# main2.net
KiCad netlist of a schematic drawn in EAGLE
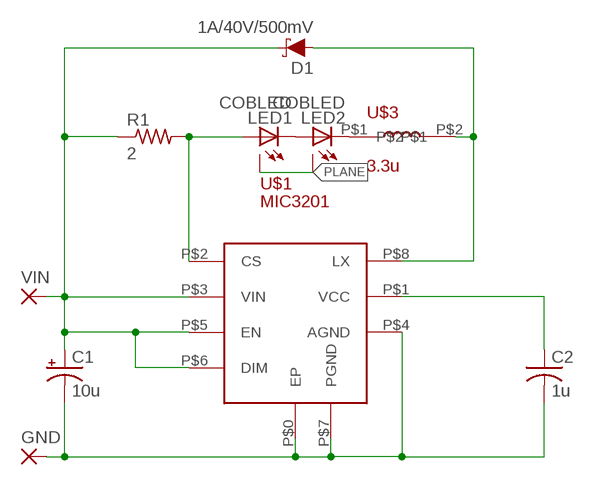
[diagram p0: schematic, sheet 1]

(export (version "E")
  (design (tool "Eeschema 10.0.6"))
  (components
    (comp (ref "C1")
      (value "10u")
      (footprint "eagle-import:E2-5")
      (libsource (lib "eagle-import") (part "CPOL-USE2-5"))
    )
    (comp (ref "C2")
      (value "1u")
      (footprint "eagle-import:C0805")
      (libsource (lib "eagle-import") (part "C-USC0805"))
    )
    (comp (ref "D1")
      (value "1A/40V/500mV")
      (footprint "eagle-import:SMA-DIODE")
      (libsource (lib "eagle-import") (part "DIODE-SCHOTTKY-SS14"))
    )
    (comp (ref "GND")
      (value "2,54/1,0")
      (footprint "eagle-import:2,54_1,0")
      (libsource (lib "eagle-import") (part "2,54/1,0"))
    )
    (comp (ref "LED1")
      (value "COBLED")
      (footprint "eagle-import:COBLED")
      (libsource (lib "eagle-import") (part "COBLED"))
    )
    (comp (ref "LED2")
      (value "COBLED")
      (footprint "eagle-import:COBLED")
      (libsource (lib "eagle-import") (part "COBLED"))
    )
    (comp (ref "R1")
      (value "2")
      (footprint "eagle-import:R0805")
      (libsource (lib "eagle-import") (part "R-US_R0805"))
    )
    (comp (ref "U$1")
      (value "MIC3201")
      (footprint "eagle-import:SOICNEP-8LD-LP-1")
      (libsource (lib "eagle-import") (part "MIC3201"))
    )
    (comp (ref "U$3")
      (value "3.3u")
      (footprint "eagle-import:DO1813H")
      (libsource (lib "eagle-import") (part "DO1813H"))
    )
    (comp (ref "VIN")
      (value "2,54/1,0")
      (footprint "eagle-import:2,54_1,0")
      (fields (field (name "SPICEPREFIX") "X"))
      (libsource (lib "eagle-import") (part "2,54/1,0"))
    )
  )
  (nets
    (net (code "1") (name "Net-(GND-P)") (class "Default")
      (node (ref "C1") (pin "-") (pinfunction "-_-") (pintype "passive"))
      (node (ref "C2") (pin "2") (pinfunction "2_2") (pintype "passive"))
      (node (ref "GND") (pin "1") (pinfunction "P_1") (pintype "passive"))
      (node (ref "U$1") (pin "P$0") (pinfunction "EP_P$0") (pintype "bidirectional"))
      (node (ref "U$1") (pin "P$4") (pinfunction "AGND_P$4") (pintype "bidirectional"))
      (node (ref "U$1") (pin "P$7") (pinfunction "PGND_P$7") (pintype "bidirectional"))
    )
    (net (code "2") (name "Net-(LED1-A)") (class "Default")
      (node (ref "LED1") (pin "P$1") (pinfunction "A_P$1") (pintype "passive"))
      (node (ref "R1") (pin "2") (pinfunction "2_2") (pintype "passive"))
      (node (ref "U$1") (pin "P$2") (pinfunction "CS_P$2") (pintype "bidirectional"))
    )
    (net (code "3") (name "Net-(LED1-C)") (class "Default")
      (node (ref "LED1") (pin "P$2") (pinfunction "C_P$2") (pintype "passive"))
      (node (ref "LED2") (pin "P$1") (pinfunction "A_P$1") (pintype "passive"))
    )
    (net (code "4") (name "Net-(LED2-C)") (class "Default")
      (node (ref "LED2") (pin "P$2") (pinfunction "C_P$2") (pintype "passive"))
      (node (ref "U$3") (pin "P$1") (pinfunction "P$1_P$1") (pintype "bidirectional"))
    )
    (net (code "5") (name "Net-(U$1-DIM)") (class "Default")
      (node (ref "C1") (pin "+") (pinfunction "+_+") (pintype "passive"))
      (node (ref "D1") (pin "C") (pinfunction "C_C") (pintype "passive"))
      (node (ref "R1") (pin "1") (pinfunction "1_1") (pintype "passive"))
      (node (ref "U$1") (pin "P$3") (pinfunction "VIN_P$3") (pintype "bidirectional"))
      (node (ref "U$1") (pin "P$5") (pinfunction "EN_P$5") (pintype "bidirectional"))
      (node (ref "U$1") (pin "P$6") (pinfunction "DIM_P$6") (pintype "bidirectional"))
      (node (ref "VIN") (pin "1") (pinfunction "P_1") (pintype "passive"))
    )
    (net (code "6") (name "Net-(U$1-LX)") (class "Default")
      (node (ref "D1") (pin "A") (pinfunction "A_A") (pintype "passive"))
      (node (ref "U$1") (pin "P$8") (pinfunction "LX_P$8") (pintype "bidirectional"))
      (node (ref "U$3") (pin "P$2") (pinfunction "P$2_P$2") (pintype "bidirectional"))
    )
    (net (code "7") (name "Net-(U$1-VCC)") (class "Default")
      (node (ref "C2") (pin "1") (pinfunction "1_1") (pintype "passive"))
      (node (ref "U$1") (pin "P$1") (pinfunction "VCC_P$1") (pintype "bidirectional"))
    )
    (net (code "8") (name "PLANE") (class "Default")
      (node (ref "LED1") (pin "P$3") (pinfunction "A1_P$3") (pintype "passive"))
      (node (ref "LED2") (pin "P$3") (pinfunction "A1_P$3") (pintype "passive"))
    )
  )
)
